# CurrentSense_isoSPI_Interface.net
KiCad netlist of a schematic drawn in Altium Designer
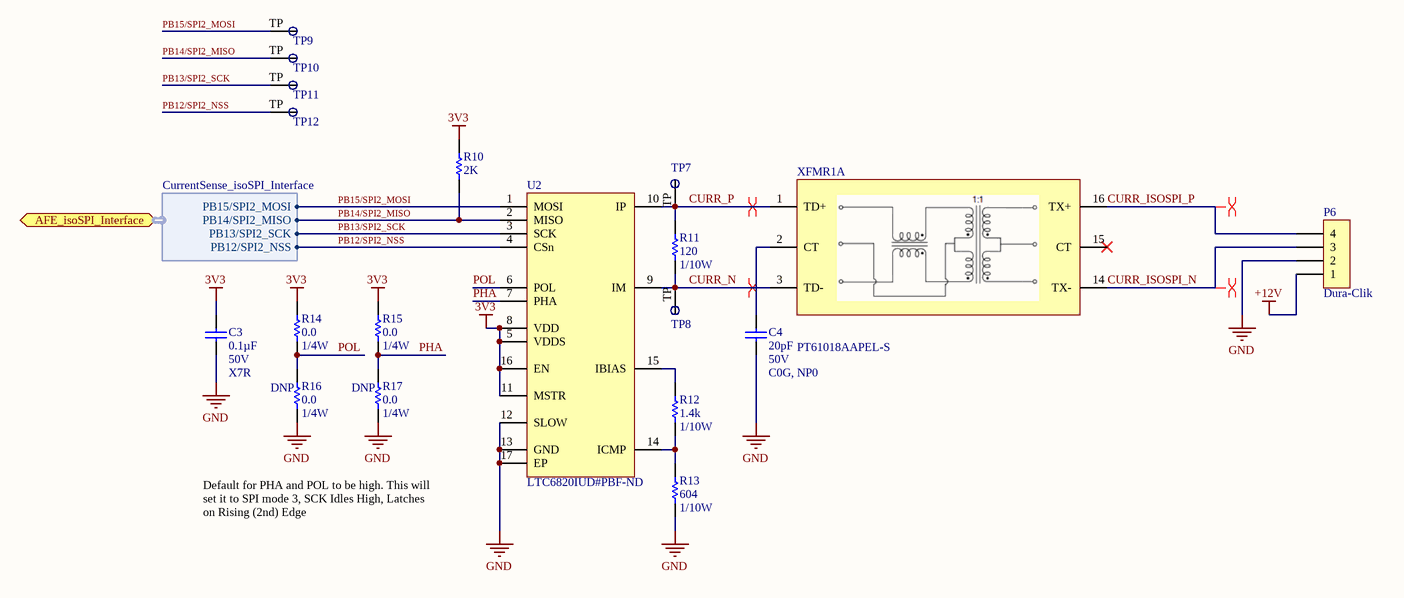
[diagram p0: CurrentSense_isoSPI_Interface.SchDoc]

(export (version "E")
  (design (tool "Eeschema 10.0.6"))
  (components
    (comp (ref "C3")
      (value "CAP CER 0.1UF 50V 10% X7R 0603")
      (footprint "CAP, 0603")
      (description "0.10µF ±10% 50V Ceramic Capacitor X7R 0603 (1608 Metric)")
      (fields
        (field (name "TOLERANCE") "±10%")
        (field (name "CAPACITANCE") "0.1µF")
        (field (name "VOLTAGE") "50V")
        (field (name "TEMPERATURE COEFFICIENT") "X7R")
      )
      (libsource (lib "Schematic Diagrams") (part "CAP CER 0.1UF 50V 10% X7R 0603"))
    )
    (comp (ref "C4")
      (value "CAP CER 20PF 50V ±5% C0G/NP0 0603")
      (footprint "CAP, 0603")
      (description "20pF ±5% 50V Ceramic Capacitor C0G, NP0 0603 (1608 Metric)")
      (fields
        (field (name "TOLERANCE") "±5%")
        (field (name "CAPACITANCE") "20pF")
        (field (name "VOLTAGE") "50V")
        (field (name "TEMPERATURE COEFFICIENT") "C0G, NP0")
      )
      (libsource (lib "Schematic Diagrams") (part "CAP CER 20PF 50V ±5% C0G/NP0 0603"))
    )
    (comp (ref "P6")
      (value "Dura-Clik")
      (footprint "CONN, 4POS DURA-CLIK VERT")
      (description "4 Positions Header Connector 0.079\" (2.00mm) Surface Mount Tin")
      (fields
        (field (name "MANUFACTURER") "Molex, LLC")
        (field (name "MANUFACTURER PART NUMBER") "5600200420")
      )
      (libsource (lib "Schematic Diagrams") (part "CONN 4POS DURA-CLIK 0.079{dblquote}"))
    )
    (comp (ref "R10")
      (value "2K")
      (footprint "RES, 0603")
      (description "2k Ohm ±1% 0.1W, 1/10W Chip Resistor 0603 (1608 Metric) Moisture Resistant Thick Film")
      (fields
        (field (name "MANUFACTURER") "Yageo")
        (field (name "MANUFACTURER PART NUMBER") "RC0603FR-072KL")
      )
      (libsource (lib "Schematic Diagrams") (part "RES 2K OHM 1% 1/10W 0603"))
    )
    (comp (ref "R11")
      (value "RES 120 OHM 1% 1/10W 0603")
      (footprint "RES, 0603")
      (description "RES SMD 120 OHM 1% 1/10W 0603")
      (fields
        (field (name "TOLERANCE") "±1%")
        (field (name "RESISTANCE") "120")
        (field (name "POWER") "1/10W")
      )
      (libsource (lib "Schematic Diagrams") (part "RES 120 OHM 1% 1/10W 0603"))
    )
    (comp (ref "R12")
      (value "RES 1.4k OHM 1% 1/10W 0603")
      (footprint "RES, 0603")
      (description "RES SMD 1.4K OHM 1% 1/10W 0603")
      (fields
        (field (name "TOLERANCE") "±1%")
        (field (name "RESISTANCE") "1.4k")
        (field (name "POWER") "1/10W")
      )
      (libsource (lib "Schematic Diagrams") (part "RES 1.4k OHM 1% 1/10W 0603"))
    )
    (comp (ref "R13")
      (value "RES 604 OHM 1% 1/10W 0603")
      (footprint "RES, 0603")
      (description "RES SMD 604 OHM 1% 1/10W 0603")
      (fields
        (field (name "TOLERANCE") "±1%")
        (field (name "RESISTANCE") "604")
        (field (name "POWER") "1/10W")
      )
      (libsource (lib "Schematic Diagrams") (part "RES 604 OHM 1% 1/10W 0603"))
    )
    (comp (ref "R14")
      (value "RES 0.0 OHM 1/4W 0603")
      (footprint "RES, 0603")
      (description "RES SMD 0.0 OHM JUMPER 1/4W 0603")
      (fields (field (name "RESISTANCE") "0.0") (field (name "POWER (WATTS)") "1/4W"))
      (libsource (lib "Schematic Diagrams") (part "RES 0.0 OHM 1/4W 0603"))
    )
    (comp (ref "R15")
      (value "RES 0.0 OHM 1/4W 0603")
      (footprint "RES, 0603")
      (description "RES SMD 0.0 OHM JUMPER 1/4W 0603")
      (fields (field (name "RESISTANCE") "0.0") (field (name "POWER (WATTS)") "1/4W"))
      (libsource (lib "Schematic Diagrams") (part "RES 0.0 OHM 1/4W 0603"))
    )
    (comp (ref "R16")
      (value "RES 0.0 OHM 1/4W 0603")
      (footprint "RES, 0603")
      (description "RES SMD 0.0 OHM JUMPER 1/4W 0603")
      (fields
        (field (name "RESISTANCE") "0.0")
        (field (name "POWER (WATTS)") "1/4W")
        (field (name "DNP") "DNP")
      )
      (libsource (lib "Schematic Diagrams") (part "RES 0.0 OHM 1/4W 0603"))
    )
    (comp (ref "R17")
      (value "RES 0.0 OHM 1/4W 0603")
      (footprint "RES, 0603")
      (description "RES SMD 0.0 OHM JUMPER 1/4W 0603")
      (fields
        (field (name "RESISTANCE") "0.0")
        (field (name "POWER (WATTS)") "1/4W")
        (field (name "DNP") "DNP")
      )
      (libsource (lib "Schematic Diagrams") (part "RES 0.0 OHM 1/4W 0603"))
    )
    (comp (ref "TP7")
      (value "Test Point")
      (footprint "Test Point")
      (libsource (lib "Schematic Diagrams") (part "Test Point"))
    )
    (comp (ref "TP8")
      (value "Test Point")
      (footprint "Test Point")
      (libsource (lib "Schematic Diagrams") (part "Test Point"))
    )
    (comp (ref "TP9")
      (value "Test Point")
      (footprint "Test Point")
      (libsource (lib "Schematic Diagrams") (part "Test Point"))
    )
    (comp (ref "TP10")
      (value "Test Point")
      (footprint "Test Point")
      (libsource (lib "Schematic Diagrams") (part "Test Point"))
    )
    (comp (ref "TP11")
      (value "Test Point")
      (footprint "Test Point")
      (libsource (lib "Schematic Diagrams") (part "Test Point"))
    )
    (comp (ref "TP12")
      (value "Test Point")
      (footprint "Test Point")
      (libsource (lib "Schematic Diagrams") (part "Test Point"))
    )
    (comp (ref "U2")
      (value "IC ISOSPI COMM INTERFACE LTC6820IUD")
      (footprint "IC COMM INTERFACE ISOSPI 16-QFN")
      (description "IC COMM INTERFACE ISOSPI 16-QFN")
      (fields
        (field (name "MANUFACTURER") "Linear Technology")
        (field (name "MANUFACTURER PART NUMBER") "LTC6820IUD#PBF")
        (field (name "SUPPLIER PART NUMBER 1") "LTC6820IUD#PBF-ND")
      )
      (libsource (lib "Schematic Diagrams") (part "IC ISOSPI COMM INTERFACE LTC6820IUD"))
    )
    (comp (ref "XFMR1")
      (value "IC PULSE XFMR 1CT:1CT 350UH SMD")
      (footprint "IC, PULSE XFMR 1CT:1CT 350UH SMD")
      (description "PULSE XFMR 1CT:1CT 350UH SMD")
      (fields (field (name "MANUFACTURER") "Bourns Inc.") (field (name "MFG_PN") "PT61018AAPEL-S"))
      (libsource (lib "Schematic Diagrams") (part "IC PULSE XFMR 1CT{colon}1CT 350UH SMD"))
    )
  )
  (nets
    (net (code "2") (name "+12V") (class "Default")
      (node (ref "P6") (pin "1") (pinfunction "1_1") (pintype "passive"))
    )
    (net (code "3") (name "/CURR_ISOSPI_N") (class "Default")
      (node (ref "P6") (pin "3") (pinfunction "3_3") (pintype "passive"))
      (node (ref "XFMR1") (pin "14") (pinfunction "TX-_14") (pintype "passive"))
    )
    (net (code "4") (name "/CURR_ISOSPI_P") (class "Default")
      (node (ref "P6") (pin "4") (pinfunction "4_4") (pintype "passive"))
      (node (ref "XFMR1") (pin "16") (pinfunction "TX+_16") (pintype "passive"))
    )
    (net (code "5") (name "/CURR_N") (class "Default")
      (node (ref "R11") (pin "2") (pinfunction "2_2") (pintype "passive"))
      (node (ref "TP8") (pin "TP") (pinfunction "1_TP") (pintype "passive"))
      (node (ref "U2") (pin "9") (pinfunction "IM_9") (pintype "passive"))
      (node (ref "XFMR1") (pin "3") (pinfunction "TD-_3") (pintype "passive"))
    )
    (net (code "6") (name "/CURR_P") (class "Default")
      (node (ref "R11") (pin "1") (pinfunction "1_1") (pintype "passive"))
      (node (ref "TP7") (pin "TP") (pinfunction "1_TP") (pintype "passive"))
      (node (ref "U2") (pin "10") (pinfunction "IP_10") (pintype "passive"))
      (node (ref "XFMR1") (pin "1") (pinfunction "TD+_1") (pintype "passive"))
    )
    (net (code "7") (name "/PB12{slash}SPI2_NSS") (class "Default")
      (node (ref "TP12") (pin "TP") (pinfunction "1_TP") (pintype "passive"))
      (node (ref "U2") (pin "4") (pinfunction "CSn_4") (pintype "passive"))
    )
    (net (code "8") (name "/PB13{slash}SPI2_SCK") (class "Default")
      (node (ref "TP11") (pin "TP") (pinfunction "1_TP") (pintype "passive"))
      (node (ref "U2") (pin "3") (pinfunction "SCK_3") (pintype "passive"))
    )
    (net (code "9") (name "/PB14{slash}SPI2_MISO") (class "Default")
      (node (ref "R10") (pin "2") (pinfunction "2_2") (pintype "passive"))
      (node (ref "TP10") (pin "TP") (pinfunction "1_TP") (pintype "passive"))
      (node (ref "U2") (pin "2") (pinfunction "MISO_2") (pintype "passive"))
    )
    (net (code "10") (name "/PB15{slash}SPI2_MOSI") (class "Default")
      (node (ref "TP9") (pin "TP") (pinfunction "1_TP") (pintype "passive"))
      (node (ref "U2") (pin "1") (pinfunction "MOSI_1") (pintype "passive"))
    )
    (net (code "11") (name "/PHA") (class "Default")
      (node (ref "R15") (pin "2") (pinfunction "2_2") (pintype "passive"))
      (node (ref "R17") (pin "1") (pinfunction "1_1") (pintype "passive"))
      (node (ref "U2") (pin "7") (pinfunction "PHA_7") (pintype "passive"))
    )
    (net (code "12") (name "/POL") (class "Default")
      (node (ref "R14") (pin "2") (pinfunction "2_2") (pintype "passive"))
      (node (ref "R16") (pin "1") (pinfunction "1_1") (pintype "passive"))
      (node (ref "U2") (pin "6") (pinfunction "POL_6") (pintype "passive"))
    )
    (net (code "14") (name "3V3") (class "Default")
      (node (ref "C3") (pin "1") (pinfunction "1_1") (pintype "passive"))
      (node (ref "R10") (pin "1") (pinfunction "1_1") (pintype "passive"))
      (node (ref "R14") (pin "1") (pinfunction "1_1") (pintype "passive"))
      (node (ref "R15") (pin "1") (pinfunction "1_1") (pintype "passive"))
      (node (ref "U2") (pin "11") (pinfunction "MSTR_11") (pintype "passive"))
      (node (ref "U2") (pin "16") (pinfunction "EN_16") (pintype "passive"))
      (node (ref "U2") (pin "5") (pinfunction "VDDS_5") (pintype "passive"))
      (node (ref "U2") (pin "8") (pinfunction "VDD_8") (pintype "passive"))
    )
    (net (code "15") (name "GND") (class "Default")
      (node (ref "C3") (pin "2") (pinfunction "2_2") (pintype "passive"))
      (node (ref "C4") (pin "2") (pinfunction "2_2") (pintype "passive"))
      (node (ref "P6") (pin "2") (pinfunction "2_2") (pintype "passive"))
      (node (ref "R13") (pin "2") (pinfunction "2_2") (pintype "passive"))
      (node (ref "R16") (pin "2") (pinfunction "2_2") (pintype "passive"))
      (node (ref "R17") (pin "2") (pinfunction "2_2") (pintype "passive"))
      (node (ref "U2") (pin "12") (pinfunction "SLOW_12") (pintype "passive"))
      (node (ref "U2") (pin "13") (pinfunction "GND_13") (pintype "passive"))
      (node (ref "U2") (pin "17") (pinfunction "EP_17") (pintype "passive"))
    )
    (net (code "16") (name "Net-(C4-Pad1)") (class "Default")
      (node (ref "C4") (pin "1") (pinfunction "1_1") (pintype "passive"))
      (node (ref "XFMR1") (pin "2") (pinfunction "CT_2") (pintype "passive"))
    )
    (net (code "17") (name "Net-(U2-IBIAS)") (class "Default")
      (node (ref "R12") (pin "1") (pinfunction "1_1") (pintype "passive"))
      (node (ref "U2") (pin "15") (pinfunction "IBIAS_15") (pintype "passive"))
    )
    (net (code "18") (name "Net-(U2-ICMP)") (class "Default")
      (node (ref "R12") (pin "2") (pinfunction "2_2") (pintype "passive"))
      (node (ref "R13") (pin "1") (pinfunction "1_1") (pintype "passive"))
      (node (ref "U2") (pin "14") (pinfunction "ICMP_14") (pintype "passive"))
    )
    (net (code "19") (name "unconnected-(XFMR1A-CT-Pad15)") (class "Default")
      (node (ref "XFMR1") (pin "15") (pinfunction "CT_15") (pintype "passive+no_connect"))
    )
  )
)
